# PowerModule.net
KiCad netlist of a schematic drawn in EAGLE
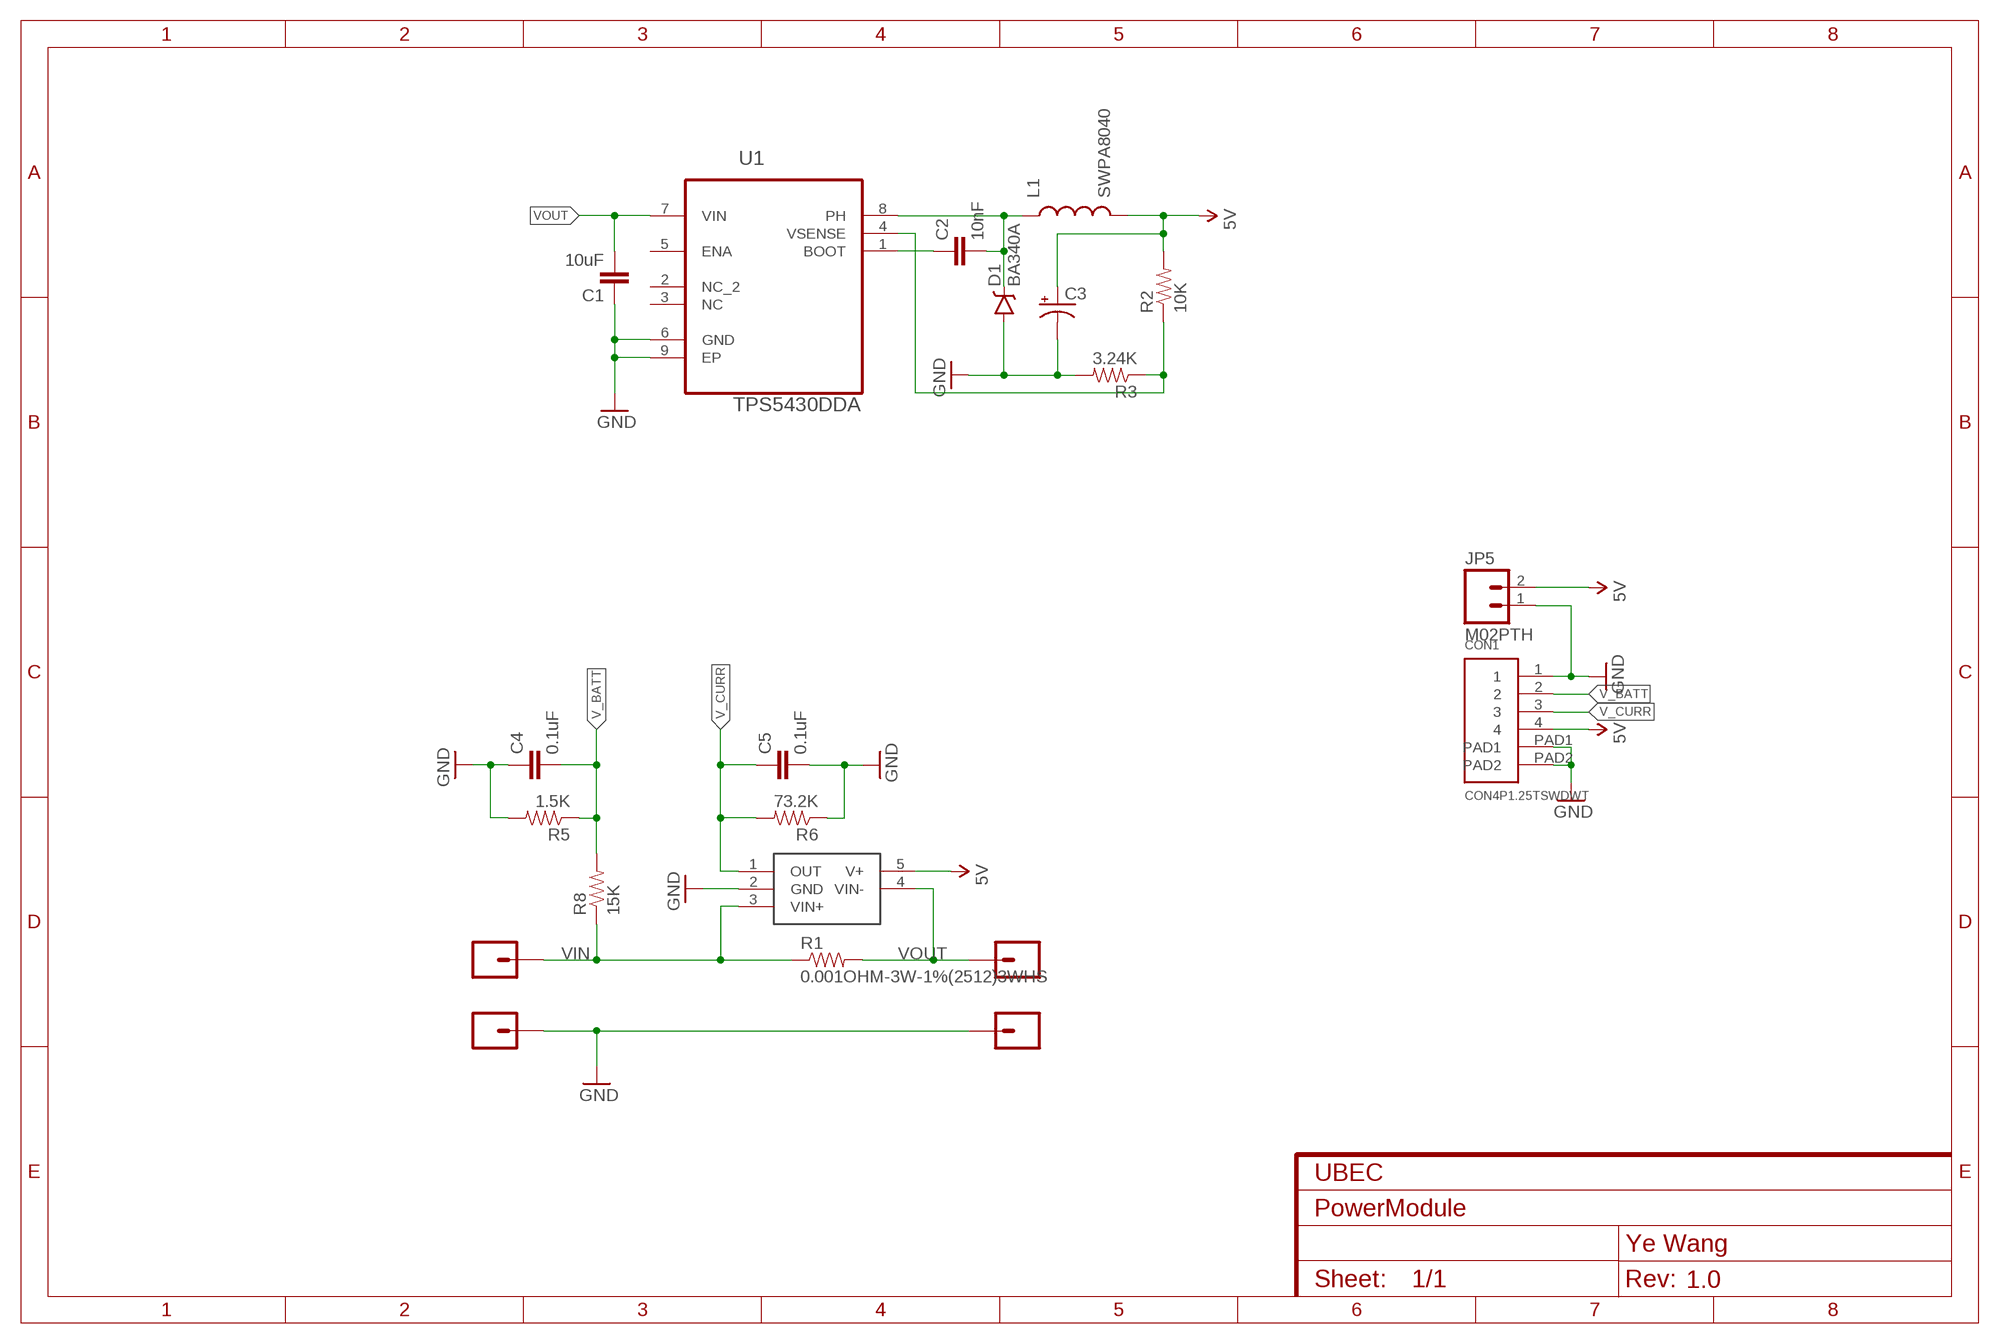
[diagram p0: schematic, sheet 1]

(export (version "E")
  (design (tool "Eeschema 10.0.6"))
  (components
    (comp (ref "C1")
      (value "10uF")
      (footprint "eagle-import:1206")
      (libsource (lib "eagle-import") (part "CAP1206"))
    )
    (comp (ref "C2")
      (value "10nF")
      (footprint "eagle-import:0603-CAP")
      (libsource (lib "eagle-import") (part "10NF/10000PF-50V-10%(0603)"))
    )
    (comp (ref "C3")
      (value "CAP_POLD")
      (footprint "eagle-import:PANASONIC_D")
      (libsource (lib "eagle-import") (part "CAP_POLD"))
    )
    (comp (ref "C4")
      (value "0.1uF")
      (footprint "eagle-import:0603-CAP")
      (libsource (lib "eagle-import") (part "0.1UF-25V-5%(0603)"))
    )
    (comp (ref "C5")
      (value "0.1uF")
      (footprint "eagle-import:0603-CAP")
      (libsource (lib "eagle-import") (part "0.1UF-25V-5%(0603)"))
    )
    (comp (ref "CON1")
      (value "CON4P1.25TSWDWT")
      (footprint "eagle-import:1.25T4P")
      (libsource (lib "eagle-import") (part "CON4P1.25TSWDWT"))
    )
    (comp (ref "D1")
      (value "BA340A")
      (footprint "eagle-import:SMA-DIODE")
      (libsource (lib "eagle-import") (part "B340A"))
    )
    (comp (ref "JP1")
      (value "M016.5X5.5")
      (footprint "eagle-import:1PAD")
      (libsource (lib "eagle-import") (part "M016.5X5.5"))
    )
    (comp (ref "JP2")
      (value "M016.5X5.5")
      (footprint "eagle-import:1PAD")
      (libsource (lib "eagle-import") (part "M016.5X5.5"))
    )
    (comp (ref "JP3")
      (value "M016.5X5.5")
      (footprint "eagle-import:1PAD")
      (libsource (lib "eagle-import") (part "M016.5X5.5"))
    )
    (comp (ref "JP4")
      (value "M016.5X5.5")
      (footprint "eagle-import:1PAD")
      (libsource (lib "eagle-import") (part "M016.5X5.5"))
    )
    (comp (ref "JP5")
      (value "M02PTH")
      (footprint "eagle-import:1X02")
      (libsource (lib "eagle-import") (part "M02PTH"))
    )
    (comp (ref "L1")
      (value "SWPA8040")
      (footprint "eagle-import:INC8040")
      (libsource (lib "eagle-import") (part "SWPA8040"))
    )
    (comp (ref "R1")
      (value "0.001OHM-3W-1%(2512)3WHS")
      (footprint "eagle-import:R2512W")
      (libsource (lib "eagle-import") (part "0.001OHM-3W-1%(2512)3WHS"))
    )
    (comp (ref "R2")
      (value "10K")
      (footprint "eagle-import:0603-RES")
      (libsource (lib "eagle-import") (part "10KOHM-1/10W-1%(0603)0603"))
    )
    (comp (ref "R3")
      (value "3.24K")
      (footprint "eagle-import:0603-RES")
      (libsource (lib "eagle-import") (part "RESISTOR0603-RES"))
    )
    (comp (ref "R5")
      (value "1.5K")
      (footprint "eagle-import:0603")
      (libsource (lib "eagle-import") (part "1.5KOHM-1/10W-1%(0603)"))
    )
    (comp (ref "R6")
      (value "73.2K")
      (footprint "eagle-import:0603-RES")
      (libsource (lib "eagle-import") (part "RESISTOR0603-RES"))
    )
    (comp (ref "R8")
      (value "15K")
      (footprint "eagle-import:0603-RES")
      (libsource (lib "eagle-import") (part "15KOHM1/10W1%(0603)0603"))
    )
    (comp (ref "U$1")
      (value "INA169")
      (footprint "eagle-import:SOT23-5")
      (libsource (lib "eagle-import") (part "INA169"))
    )
    (comp (ref "U1")
      (value "TPS5430DDA")
      (footprint "eagle-import:SOIC127P600X170-9N")
      (libsource (lib "eagle-import") (part "TPS5430DDA"))
    )
  )
  (nets
    (net (code "1") (name "/VIN") (class "Default")
      (node (ref "JP1") (pin "1") (pinfunction "1_1") (pintype "passive"))
      (node (ref "R1") (pin "1") (pinfunction "1_1") (pintype "passive"))
      (node (ref "R8") (pin "1") (pinfunction "1_1") (pintype "passive"))
      (node (ref "U$1") (pin "3") (pinfunction "VIN+_3") (pintype "bidirectional"))
    )
    (net (code "2") (name "5V") (class "Default")
      (node (ref "C3") (pin "+") (pinfunction "+_+") (pintype "passive"))
      (node (ref "CON1") (pin "4") (pinfunction "4_4") (pintype "bidirectional"))
      (node (ref "JP5") (pin "2") (pinfunction "2_2") (pintype "passive"))
      (node (ref "L1") (pin "2") (pinfunction "2_2") (pintype "passive"))
      (node (ref "R2") (pin "2") (pinfunction "2_2") (pintype "passive"))
      (node (ref "U$1") (pin "5") (pinfunction "V+_5") (pintype "bidirectional"))
    )
    (net (code "3") (name "GND") (class "Default")
      (node (ref "C1") (pin "1") (pinfunction "1_1") (pintype "passive"))
      (node (ref "C3") (pin "-") (pinfunction "-_-") (pintype "passive"))
      (node (ref "C4") (pin "1") (pinfunction "1_1") (pintype "passive"))
      (node (ref "C5") (pin "2") (pinfunction "2_2") (pintype "passive"))
      (node (ref "CON1") (pin "1") (pinfunction "1_1") (pintype "bidirectional"))
      (node (ref "CON1") (pin "PAD1") (pinfunction "PAD1_PAD1") (pintype "bidirectional"))
      (node (ref "CON1") (pin "PAD2") (pinfunction "PAD2_PAD2") (pintype "bidirectional"))
      (node (ref "D1") (pin "A") (pinfunction "A_A") (pintype "passive"))
      (node (ref "JP3") (pin "1") (pinfunction "1_1") (pintype "passive"))
      (node (ref "JP4") (pin "1") (pinfunction "1_1") (pintype "passive"))
      (node (ref "JP5") (pin "1") (pinfunction "1_1") (pintype "passive"))
      (node (ref "R3") (pin "2") (pinfunction "2_2") (pintype "passive"))
      (node (ref "R5") (pin "2") (pinfunction "2_2") (pintype "passive"))
      (node (ref "R6") (pin "1") (pinfunction "1_1") (pintype "passive"))
      (node (ref "U$1") (pin "2") (pinfunction "GND_2") (pintype "bidirectional"))
      (node (ref "U1") (pin "6") (pinfunction "GND_6") (pintype "passive"))
      (node (ref "U1") (pin "9") (pinfunction "EP_9") (pintype "passive"))
    )
    (net (code "4") (name "Net-(U1-BOOT)") (class "Default")
      (node (ref "C2") (pin "1") (pinfunction "1_1") (pintype "passive"))
      (node (ref "U1") (pin "1") (pinfunction "BOOT_1") (pintype "passive"))
    )
    (net (code "5") (name "Net-(U1-PH)") (class "Default")
      (node (ref "C2") (pin "2") (pinfunction "2_2") (pintype "passive"))
      (node (ref "D1") (pin "C") (pinfunction "C_C") (pintype "passive"))
      (node (ref "L1") (pin "1") (pinfunction "1_1") (pintype "passive"))
      (node (ref "U1") (pin "8") (pinfunction "PH_8") (pintype "output"))
    )
    (net (code "6") (name "Net-(U1-VSENSE)") (class "Default")
      (node (ref "R2") (pin "1") (pinfunction "1_1") (pintype "passive"))
      (node (ref "R3") (pin "1") (pinfunction "1_1") (pintype "passive"))
      (node (ref "U1") (pin "4") (pinfunction "VSENSE_4") (pintype "output"))
    )
    (net (code "7") (name "VOUT") (class "Default")
      (node (ref "C1") (pin "2") (pinfunction "2_2") (pintype "passive"))
      (node (ref "JP2") (pin "1") (pinfunction "1_1") (pintype "passive"))
      (node (ref "R1") (pin "2") (pinfunction "2_2") (pintype "passive"))
      (node (ref "U$1") (pin "4") (pinfunction "VIN-_4") (pintype "bidirectional"))
      (node (ref "U1") (pin "7") (pinfunction "VIN_7") (pintype "input"))
    )
    (net (code "8") (name "V_BATT") (class "Default")
      (node (ref "C4") (pin "2") (pinfunction "2_2") (pintype "passive"))
      (node (ref "CON1") (pin "2") (pinfunction "2_2") (pintype "bidirectional"))
      (node (ref "R5") (pin "1") (pinfunction "1_1") (pintype "passive"))
      (node (ref "R8") (pin "2") (pinfunction "2_2") (pintype "passive"))
    )
    (net (code "9") (name "V_CURR") (class "Default")
      (node (ref "C5") (pin "1") (pinfunction "1_1") (pintype "passive"))
      (node (ref "CON1") (pin "3") (pinfunction "3_3") (pintype "bidirectional"))
      (node (ref "R6") (pin "2") (pinfunction "2_2") (pintype "passive"))
      (node (ref "U$1") (pin "1") (pinfunction "OUT_1") (pintype "bidirectional"))
    )
    (net (code "10") (name "unconnected-(U1-ENA-Pad5)") (class "Default")
      (node (ref "U1") (pin "5") (pinfunction "ENA_5") (pintype "input"))
    )
    (net (code "11") (name "unconnected-(U1-NC-Pad3)") (class "Default")
      (node (ref "U1") (pin "3") (pinfunction "NC_3") (pintype "no_connect"))
    )
    (net (code "12") (name "unconnected-(U1-NC_2-Pad2)") (class "Default")
      (node (ref "U1") (pin "2") (pinfunction "NC_2_2") (pintype "no_connect"))
    )
  )
)
